# TOP.net
KiCad netlist of a schematic drawn in Altium Designer
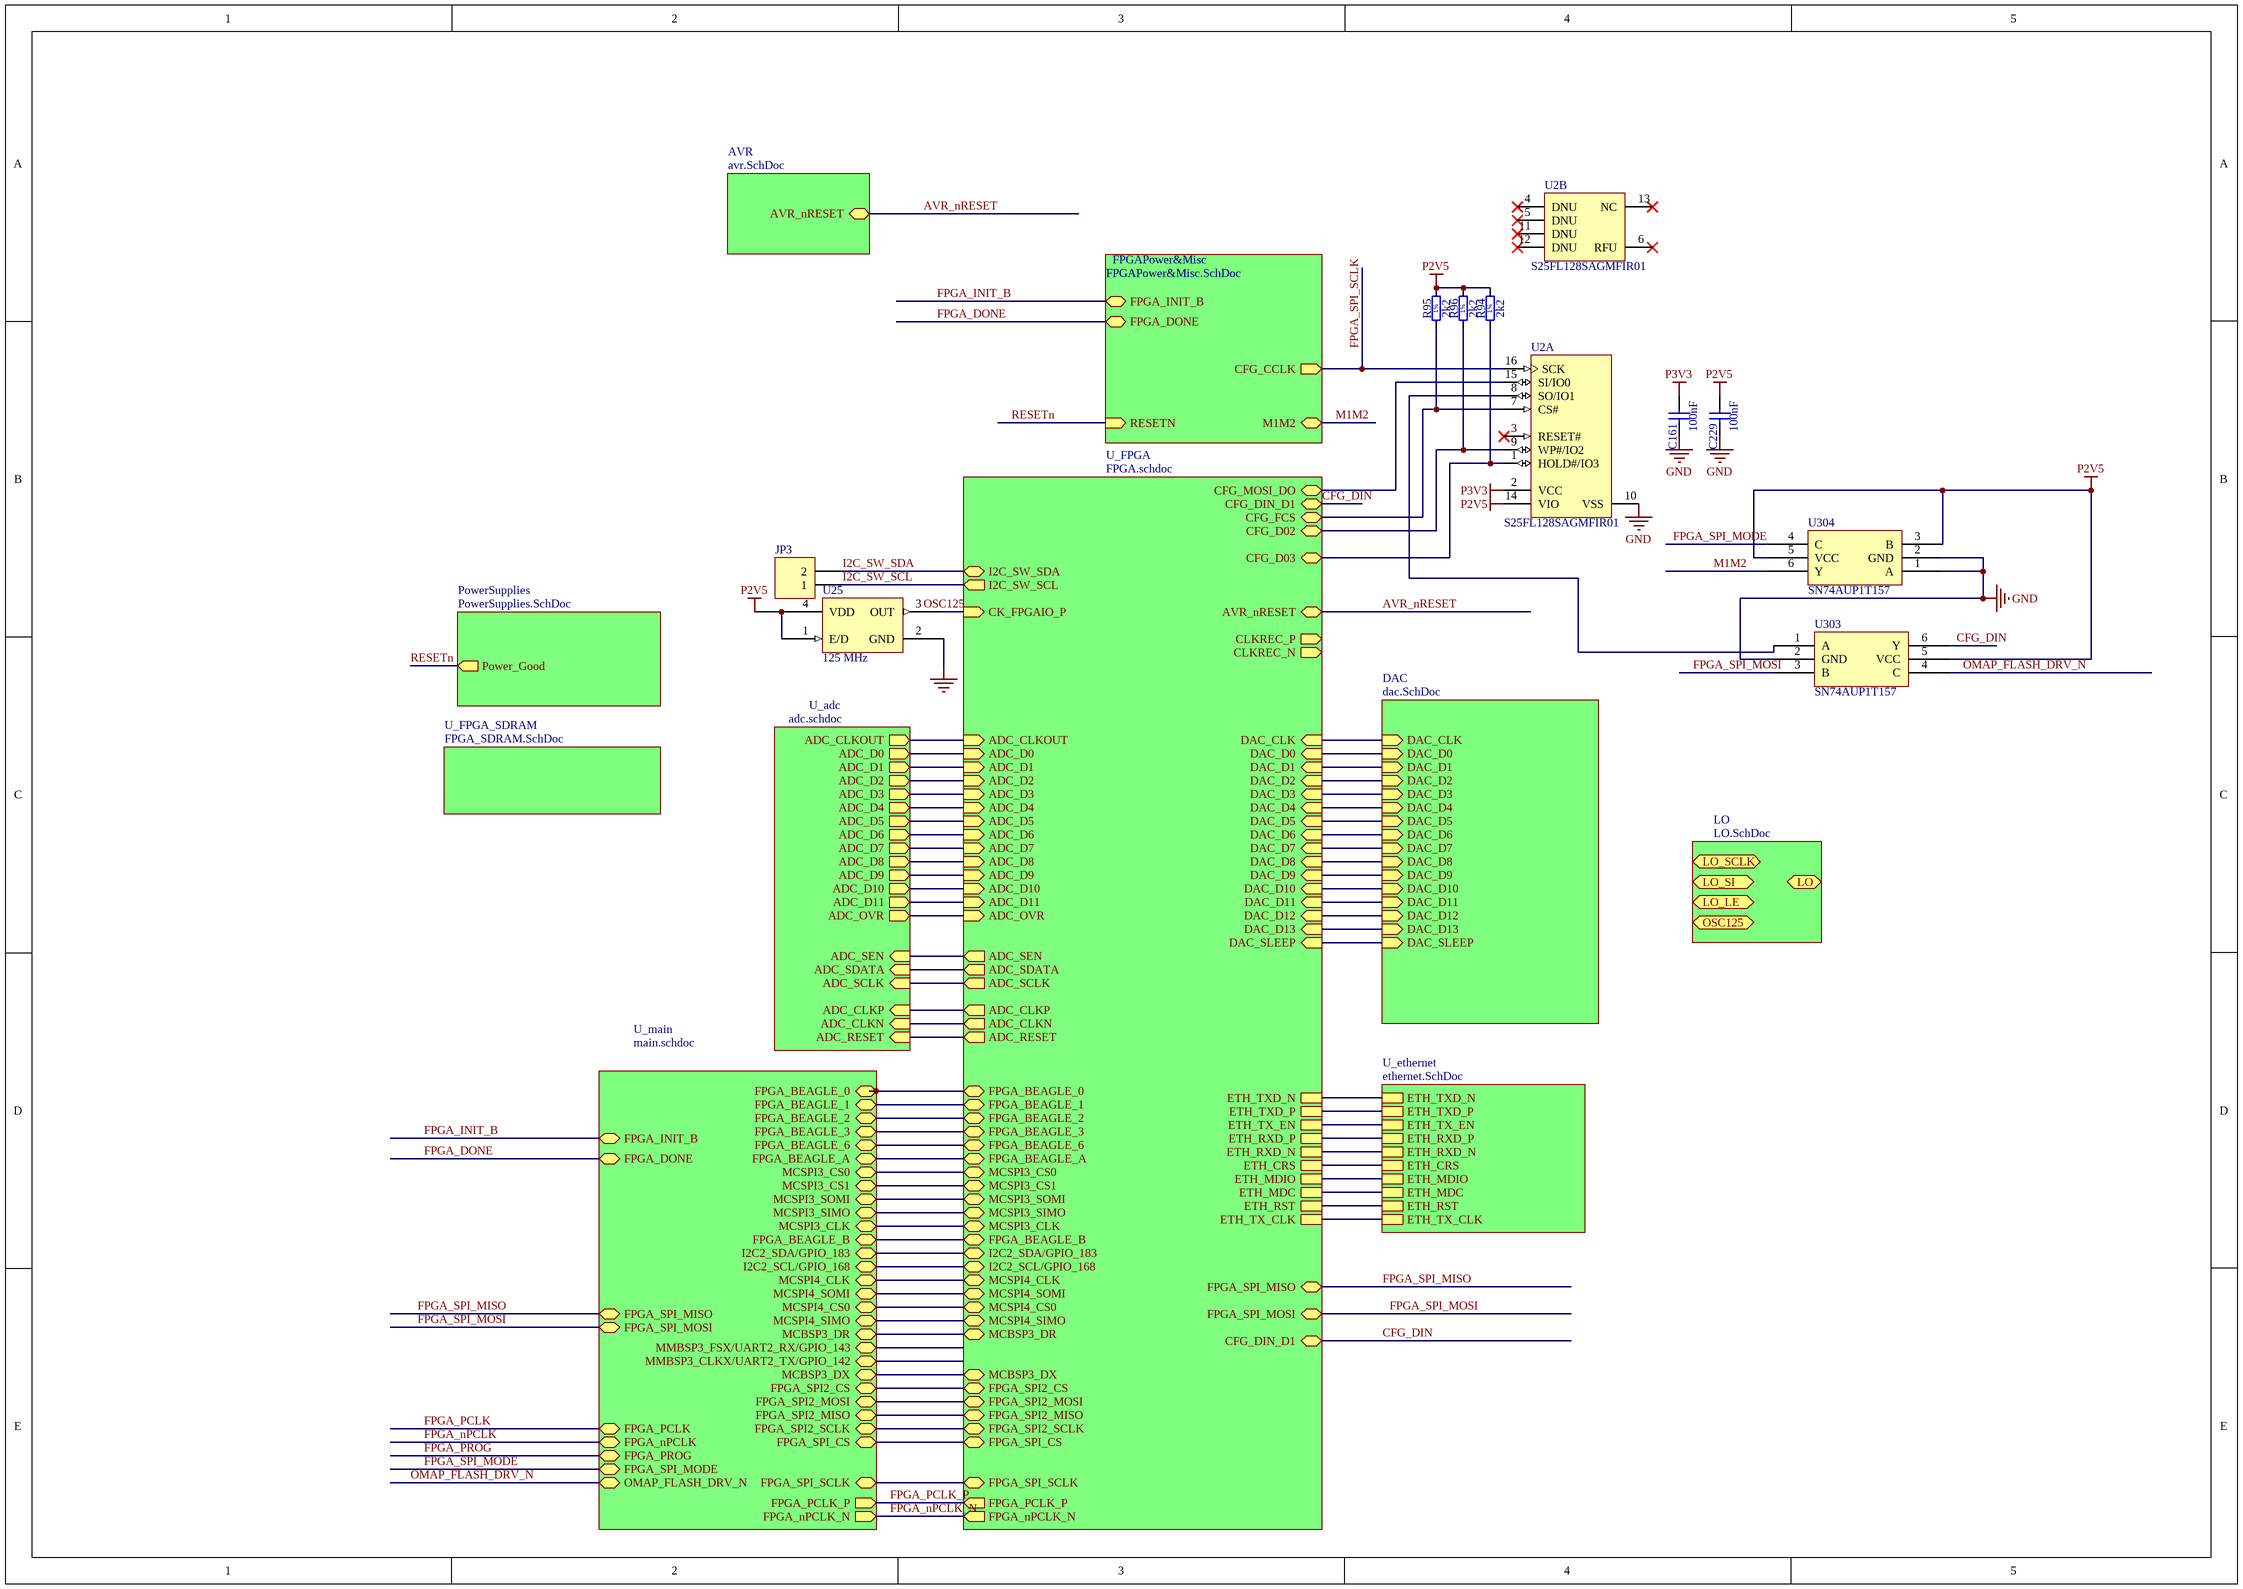
[diagram p0: TOP.SchDoc]

(export (version "E")
  (design (tool "Eeschema 10.0.6"))
  (components
    (comp (ref "C161")
      (value "100nF")
      (footprint "0603 Polar Cap")
      (description "Non-polarised capacitor")
      (fields
        (field (name "PART NUMBER") "CC0201_100NF_6.3V_10%_X5R")
        (field (name "VOLTAGE") "6.3V")
        (field (name "AUTHOR") "CERN DEM JLC")
      )
      (libsource (lib "Capacitors") (part "Capacitor - non polarized"))
    )
    (comp (ref "C229")
      (value "100nF")
      (footprint "0603 Polar Cap")
      (description "Non-polarised capacitor")
      (fields
        (field (name "PART NUMBER") "CC0201_100NF_6.3V_10%_X5R")
        (field (name "VOLTAGE") "6.3V")
        (field (name "AUTHOR") "CERN DEM JLC")
      )
      (libsource (lib "Capacitors") (part "Capacitor - non polarized"))
    )
    (comp (ref "JP3")
      (value "~")
      (footprint "HDR1X2")
      (description "Header, 2-Pin")
      (fields (field (name "PUBLISHER") "Altium Limited"))
      (libsource (lib "Miscellaneous Connectors") (part "Header 2"))
    )
    (comp (ref "R94")
      (value "2k2")
      (footprint "RESC1005X40N")
      (description "Resistor - 1%")
      (fields
        (field (name "PART NUMBER") "R0402_2K2_1%_0.0625W_100PPM")
        (field (name "POWER") "0.0625W")
        (field (name "AUTHOR") "CERN DEM JLC")
      )
      (libsource (lib "Resistors") (part "Resistor - 1%"))
    )
    (comp (ref "R95")
      (value "2k2")
      (footprint "RESC1005X40N")
      (description "Resistor - 1%")
      (fields
        (field (name "PART NUMBER") "R0402_2K2_1%_0.0625W_100PPM")
        (field (name "POWER") "0.0625W")
        (field (name "AUTHOR") "CERN DEM JLC")
      )
      (libsource (lib "Resistors") (part "Resistor - 1%"))
    )
    (comp (ref "R96")
      (value "2k2")
      (footprint "RESC1005X40N")
      (description "Resistor - 1%")
      (fields
        (field (name "PART NUMBER") "R0402_2K2_1%_0.0625W_100PPM")
        (field (name "POWER") "0.0625W")
        (field (name "AUTHOR") "CERN DEM JLC")
      )
      (libsource (lib "Resistors") (part "Resistor - 1%"))
    )
    (comp (ref "U2")
      (value "S25FL128SAGMFIR01")
      (footprint "SPSN-SOIC-16_N")
      (fields (field (name "MANUFACTURER") "Spansion"))
      (libsource (lib "altium-import") (part "root_0_SPSN-S25FL128S-16_A_"))
    )
    (comp (ref "U25")
      (value "125 MHz")
      (footprint "CSX750FB")
      (description "CWX815-125.0M")
      (fields (field (name "PART NO.") "CW585TR-ND") (field (name "MANUFACTURER") "Citizen America"))
      (libsource (lib "minisdr") (part "CWX815-100.0M"))
    )
    (comp (ref "U303")
      (value "SN74AUP1T157")
      (footprint "SOT363")
      (libsource (lib "SN74AUP1T157") (part "SN74AUP1T157"))
    )
    (comp (ref "U304")
      (value "SN74AUP1T157")
      (footprint "SOT363")
      (libsource (lib "SN74AUP1T157") (part "N74AUP1T157"))
    )
  )
  (nets
    (net (code "22") (name "/CFG_D02") (class "Default")
      (node (ref "R96") (pin "1") (pinfunction "1_1") (pintype "passive"))
      (node (ref "U2") (pin "9") (pinfunction "WP#/IO2_9") (pintype "bidirectional"))
    )
    (net (code "23") (name "/CFG_D03") (class "Default")
      (node (ref "R94") (pin "1") (pinfunction "1_1") (pintype "passive"))
      (node (ref "U2") (pin "1") (pinfunction "HOLD#/IO3_1") (pintype "bidirectional"))
    )
    (net (code "24") (name "/CFG_DIN") (class "Default")
      (node (ref "U303") (pin "6") (pinfunction "Y_6") (pintype "passive"))
    )
    (net (code "25") (name "/CFG_FCS") (class "Default")
      (node (ref "R95") (pin "1") (pinfunction "1_1") (pintype "passive"))
      (node (ref "U2") (pin "7") (pinfunction "CS#_7") (pintype "input"))
    )
    (net (code "26") (name "/CFG_MOSI_DO") (class "Default")
      (node (ref "U2") (pin "15") (pinfunction "SI/IO0_15") (pintype "bidirectional"))
    )
    (net (code "27") (name "/CK_FPGAIO_P") (class "Default")
      (node (ref "U25") (pin "3") (pinfunction "OUT_3") (pintype "output"))
    )
    (net (code "74") (name "/FPGA_SPI_MODE") (class "Default")
      (node (ref "U304") (pin "4") (pinfunction "C_4") (pintype "passive"))
    )
    (net (code "75") (name "/FPGA_SPI_MOSI") (class "Default")
      (node (ref "U303") (pin "3") (pinfunction "B_3") (pintype "passive"))
    )
    (net (code "76") (name "/FPGA_SPI_SCLK") (class "Default")
      (node (ref "U2") (pin "16") (pinfunction "SCK_16") (pintype "input"))
    )
    (net (code "82") (name "/I2C_SW_SCL") (class "Default")
      (node (ref "JP3") (pin "1") (pinfunction "1_1") (pintype "passive"))
    )
    (net (code "83") (name "/I2C_SW_SDA") (class "Default")
      (node (ref "JP3") (pin "2") (pinfunction "2_2") (pintype "passive"))
    )
    (net (code "88") (name "/M1M2") (class "Default")
      (node (ref "U304") (pin "6") (pinfunction "Y_6") (pintype "passive"))
    )
    (net (code "102") (name "/OMAP_FLASH_DRV_N") (class "Default")
      (node (ref "U303") (pin "4") (pinfunction "C_4") (pintype "passive"))
    )
    (net (code "105") (name "GND") (class "Default")
      (node (ref "C161") (pin "1") (pinfunction "1_1") (pintype "passive"))
      (node (ref "C229") (pin "1") (pinfunction "1_1") (pintype "passive"))
      (node (ref "U2") (pin "10") (pinfunction "VSS_10") (pintype "power_in"))
      (node (ref "U25") (pin "2") (pinfunction "GND_2") (pintype "passive"))
      (node (ref "U303") (pin "2") (pinfunction "GND_2") (pintype "passive"))
      (node (ref "U304") (pin "1") (pinfunction "A_1") (pintype "passive"))
      (node (ref "U304") (pin "2") (pinfunction "GND_2") (pintype "passive"))
    )
    (net (code "106") (name "Net-(U2A-SO{slash}IO1)") (class "Default")
      (node (ref "U2") (pin "8") (pinfunction "SO/IO1_8") (pintype "bidirectional"))
      (node (ref "U303") (pin "1") (pinfunction "A_1") (pintype "passive"))
    )
    (net (code "107") (name "P2V5") (class "Default")
      (node (ref "C229") (pin "2") (pinfunction "2_2") (pintype "passive"))
      (node (ref "R94") (pin "2") (pinfunction "2_2") (pintype "passive"))
      (node (ref "R95") (pin "2") (pinfunction "2_2") (pintype "passive"))
      (node (ref "R96") (pin "2") (pinfunction "2_2") (pintype "passive"))
      (node (ref "U2") (pin "14") (pinfunction "VIO_14") (pintype "power_in"))
      (node (ref "U25") (pin "1") (pinfunction "E/D_1") (pintype "input"))
      (node (ref "U25") (pin "4") (pinfunction "VDD_4") (pintype "power_in"))
      (node (ref "U303") (pin "5") (pinfunction "VCC_5") (pintype "passive"))
      (node (ref "U304") (pin "3") (pinfunction "B_3") (pintype "passive"))
      (node (ref "U304") (pin "5") (pinfunction "VCC_5") (pintype "passive"))
    )
    (net (code "108") (name "P3V3") (class "Default")
      (node (ref "C161") (pin "2") (pinfunction "2_2") (pintype "passive"))
      (node (ref "U2") (pin "2") (pinfunction "VCC_2") (pintype "power_in"))
    )
    (net (code "109") (name "unconnected-(U2A-RESET#-Pad3)") (class "Default")
      (node (ref "U2") (pin "3") (pinfunction "RESET#_3") (pintype "input+no_connect"))
    )
    (net (code "110") (name "unconnected-(U2B-DNU-Pad4)") (class "Default")
      (node (ref "U2") (pin "4") (pinfunction "DNU_4") (pintype "passive+no_connect"))
    )
    (net (code "111") (name "unconnected-(U2B-DNU-Pad5)") (class "Default")
      (node (ref "U2") (pin "5") (pinfunction "DNU_5") (pintype "passive+no_connect"))
    )
    (net (code "112") (name "unconnected-(U2B-DNU-Pad11)") (class "Default")
      (node (ref "U2") (pin "11") (pinfunction "DNU_11") (pintype "passive+no_connect"))
    )
    (net (code "113") (name "unconnected-(U2B-DNU-Pad12)") (class "Default")
      (node (ref "U2") (pin "12") (pinfunction "DNU_12") (pintype "passive+no_connect"))
    )
    (net (code "114") (name "unconnected-(U2B-NC-Pad13)") (class "Default")
      (node (ref "U2") (pin "13") (pinfunction "NC_13") (pintype "passive+no_connect"))
    )
    (net (code "115") (name "unconnected-(U2B-RFU-Pad6)") (class "Default")
      (node (ref "U2") (pin "6") (pinfunction "RFU_6") (pintype "passive+no_connect"))
    )
  )
)
